# PMTConn.net
KiCad netlist of a schematic drawn in EAGLE
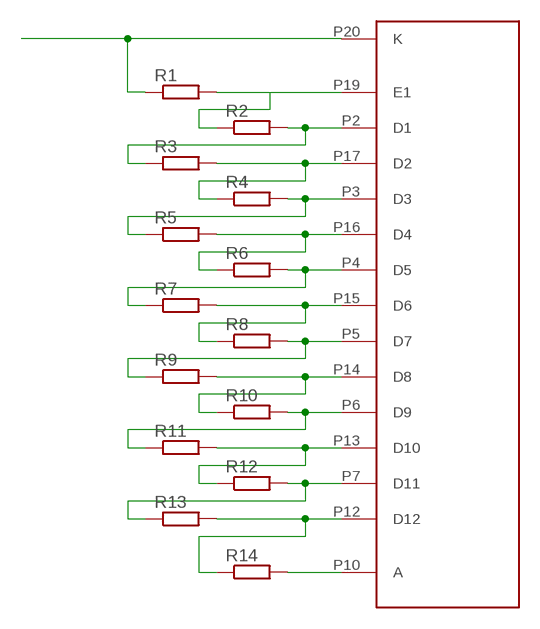
[diagram p0: schematic, sheet 1]

(export (version "E")
  (design (tool "Eeschema 10.0.6"))
  (components
    (comp (ref "R1")
      (value "R-EU_0207/2V")
      (footprint "eagle-import:0207_2V")
      (libsource (lib "eagle-import") (part "R-EU_0207/2V"))
    )
    (comp (ref "R2")
      (value "R-EU_0207/2V")
      (footprint "eagle-import:0207_2V")
      (libsource (lib "eagle-import") (part "R-EU_0207/2V"))
    )
    (comp (ref "R3")
      (value "R-EU_0207/2V")
      (footprint "eagle-import:0207_2V")
      (libsource (lib "eagle-import") (part "R-EU_0207/2V"))
    )
    (comp (ref "R4")
      (value "R-EU_0207/2V")
      (footprint "eagle-import:0207_2V")
      (libsource (lib "eagle-import") (part "R-EU_0207/2V"))
    )
    (comp (ref "R5")
      (value "R-EU_0207/2V")
      (footprint "eagle-import:0207_2V")
      (libsource (lib "eagle-import") (part "R-EU_0207/2V"))
    )
    (comp (ref "R6")
      (value "R-EU_0207/2V")
      (footprint "eagle-import:0207_2V")
      (libsource (lib "eagle-import") (part "R-EU_0207/2V"))
    )
    (comp (ref "R7")
      (value "R-EU_0207/2V")
      (footprint "eagle-import:0207_2V")
      (libsource (lib "eagle-import") (part "R-EU_0207/2V"))
    )
    (comp (ref "R8")
      (value "R-EU_0207/2V")
      (footprint "eagle-import:0207_2V")
      (libsource (lib "eagle-import") (part "R-EU_0207/2V"))
    )
    (comp (ref "R9")
      (value "R-EU_0207/2V")
      (footprint "eagle-import:0207_2V")
      (libsource (lib "eagle-import") (part "R-EU_0207/2V"))
    )
    (comp (ref "R10")
      (value "R-EU_0207/2V")
      (footprint "eagle-import:0207_2V")
      (libsource (lib "eagle-import") (part "R-EU_0207/2V"))
    )
    (comp (ref "R11")
      (value "R-EU_0207/2V")
      (footprint "eagle-import:0207_2V")
      (libsource (lib "eagle-import") (part "R-EU_0207/2V"))
    )
    (comp (ref "R12")
      (value "R-EU_0207/2V")
      (footprint "eagle-import:0207_2V")
      (libsource (lib "eagle-import") (part "R-EU_0207/2V"))
    )
    (comp (ref "R13")
      (value "R-EU_0207/2V")
      (footprint "eagle-import:0207_2V")
      (libsource (lib "eagle-import") (part "R-EU_0207/2V"))
    )
    (comp (ref "R14")
      (value "R-EU_0207/2V")
      (footprint "eagle-import:0207_2V")
      (libsource (lib "eagle-import") (part "R-EU_0207/2V"))
    )
    (comp (ref "U$1")
      (value "M12FQC51")
      (footprint "eagle-import:PMT")
      (libsource (lib "eagle-import") (part "M12FQC51"))
    )
  )
  (nets
    (net (code "1") (name "Net-(U$1-A)") (class "Default")
      (node (ref "R14") (pin "2") (pinfunction "2_2") (pintype "passive"))
      (node (ref "U$1") (pin "P10") (pinfunction "A_P10") (pintype "bidirectional"))
    )
    (net (code "2") (name "Net-(U$1-D1)") (class "Default")
      (node (ref "R2") (pin "2") (pinfunction "2_2") (pintype "passive"))
      (node (ref "R3") (pin "1") (pinfunction "1_1") (pintype "passive"))
      (node (ref "U$1") (pin "P2") (pinfunction "D1_P2") (pintype "bidirectional"))
    )
    (net (code "3") (name "Net-(U$1-D2)") (class "Default")
      (node (ref "R3") (pin "2") (pinfunction "2_2") (pintype "passive"))
      (node (ref "R4") (pin "1") (pinfunction "1_1") (pintype "passive"))
      (node (ref "U$1") (pin "P17") (pinfunction "D2_P17") (pintype "bidirectional"))
    )
    (net (code "4") (name "Net-(U$1-D3)") (class "Default")
      (node (ref "R4") (pin "2") (pinfunction "2_2") (pintype "passive"))
      (node (ref "R5") (pin "1") (pinfunction "1_1") (pintype "passive"))
      (node (ref "U$1") (pin "P3") (pinfunction "D3_P3") (pintype "bidirectional"))
    )
    (net (code "5") (name "Net-(U$1-D4)") (class "Default")
      (node (ref "R5") (pin "2") (pinfunction "2_2") (pintype "passive"))
      (node (ref "R6") (pin "1") (pinfunction "1_1") (pintype "passive"))
      (node (ref "U$1") (pin "P16") (pinfunction "D4_P16") (pintype "bidirectional"))
    )
    (net (code "6") (name "Net-(U$1-D5)") (class "Default")
      (node (ref "R6") (pin "2") (pinfunction "2_2") (pintype "passive"))
      (node (ref "R7") (pin "1") (pinfunction "1_1") (pintype "passive"))
      (node (ref "U$1") (pin "P4") (pinfunction "D5_P4") (pintype "bidirectional"))
    )
    (net (code "7") (name "Net-(U$1-D6)") (class "Default")
      (node (ref "R7") (pin "2") (pinfunction "2_2") (pintype "passive"))
      (node (ref "R8") (pin "1") (pinfunction "1_1") (pintype "passive"))
      (node (ref "U$1") (pin "P15") (pinfunction "D6_P15") (pintype "bidirectional"))
    )
    (net (code "8") (name "Net-(U$1-D7)") (class "Default")
      (node (ref "R8") (pin "2") (pinfunction "2_2") (pintype "passive"))
      (node (ref "R9") (pin "1") (pinfunction "1_1") (pintype "passive"))
      (node (ref "U$1") (pin "P5") (pinfunction "D7_P5") (pintype "bidirectional"))
    )
    (net (code "9") (name "Net-(U$1-D8)") (class "Default")
      (node (ref "R10") (pin "1") (pinfunction "1_1") (pintype "passive"))
      (node (ref "R9") (pin "2") (pinfunction "2_2") (pintype "passive"))
      (node (ref "U$1") (pin "P14") (pinfunction "D8_P14") (pintype "bidirectional"))
    )
    (net (code "10") (name "Net-(U$1-D9)") (class "Default")
      (node (ref "R10") (pin "2") (pinfunction "2_2") (pintype "passive"))
      (node (ref "R11") (pin "1") (pinfunction "1_1") (pintype "passive"))
      (node (ref "U$1") (pin "P6") (pinfunction "D9_P6") (pintype "bidirectional"))
    )
    (net (code "11") (name "Net-(U$1-D10)") (class "Default")
      (node (ref "R11") (pin "2") (pinfunction "2_2") (pintype "passive"))
      (node (ref "R12") (pin "1") (pinfunction "1_1") (pintype "passive"))
      (node (ref "U$1") (pin "P13") (pinfunction "D10_P13") (pintype "bidirectional"))
    )
    (net (code "12") (name "Net-(U$1-D11)") (class "Default")
      (node (ref "R12") (pin "2") (pinfunction "2_2") (pintype "passive"))
      (node (ref "R13") (pin "1") (pinfunction "1_1") (pintype "passive"))
      (node (ref "U$1") (pin "P7") (pinfunction "D11_P7") (pintype "bidirectional"))
    )
    (net (code "13") (name "Net-(U$1-D12)") (class "Default")
      (node (ref "R13") (pin "2") (pinfunction "2_2") (pintype "passive"))
      (node (ref "R14") (pin "1") (pinfunction "1_1") (pintype "passive"))
      (node (ref "U$1") (pin "P12") (pinfunction "D12_P12") (pintype "bidirectional"))
    )
    (net (code "14") (name "Net-(U$1-E1)") (class "Default")
      (node (ref "R1") (pin "2") (pinfunction "2_2") (pintype "passive"))
      (node (ref "R2") (pin "1") (pinfunction "1_1") (pintype "passive"))
      (node (ref "U$1") (pin "P19") (pinfunction "E1_P19") (pintype "bidirectional"))
    )
    (net (code "15") (name "Net-(U$1-K)") (class "Default")
      (node (ref "R1") (pin "1") (pinfunction "1_1") (pintype "passive"))
      (node (ref "U$1") (pin "P20") (pinfunction "K_P20") (pintype "bidirectional"))
    )
  )
)
